# BMW_final_CH_Label.net
KiCad netlist of a schematic drawn in EAGLE
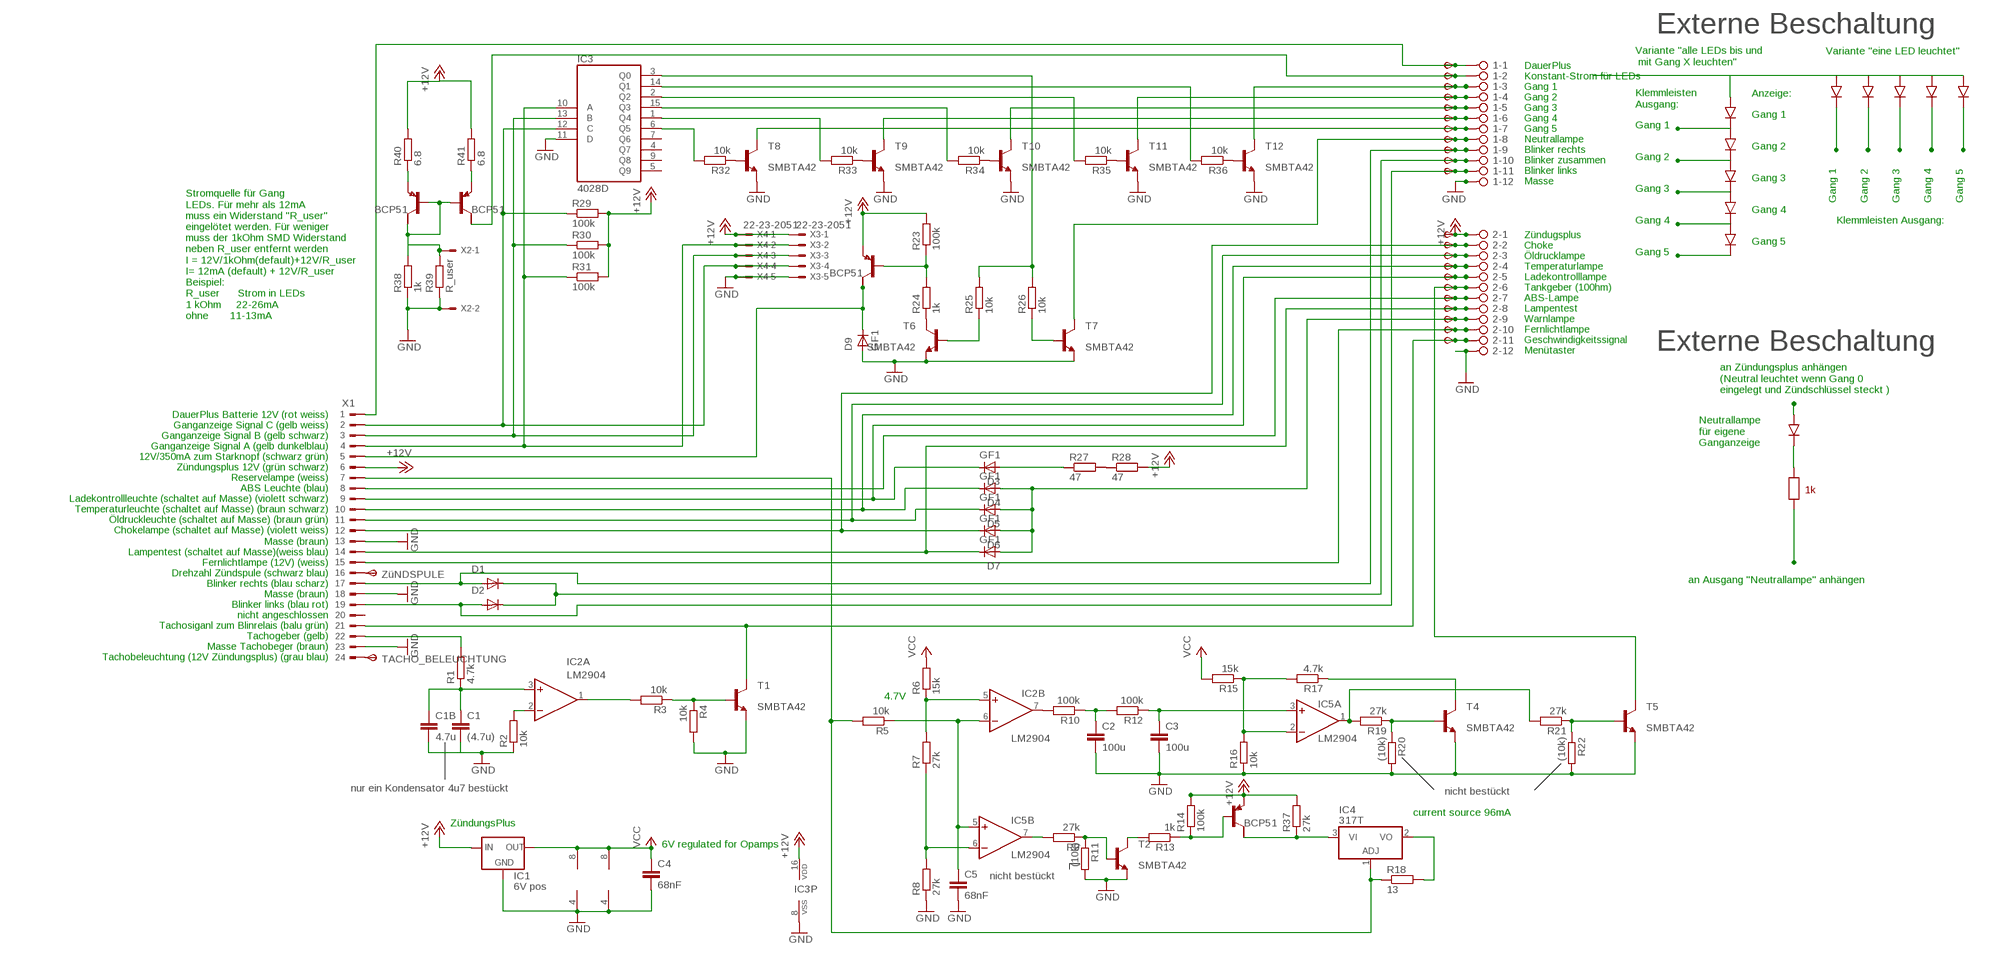
[diagram p0: schematic, sheet 1]

(export (version "E")
  (design (tool "Eeschema 10.0.6"))
  (components
    (comp (ref "1")
      (value "2081-1132")
      (footprint "eagle-import:12-PIN")
      (libsource (lib "eagle-import") (part "2081-1132"))
    )
    (comp (ref "2")
      (value "2081-1132")
      (footprint "eagle-import:12-PIN")
      (libsource (lib "eagle-import") (part "2081-1132"))
    )
    (comp (ref "C1")
      (value "(4.7u)")
      (footprint "eagle-import:C1206")
      (libsource (lib "eagle-import") (part "C-EUC1206"))
    )
    (comp (ref "C1B")
      (value "4.7u")
      (footprint "eagle-import:C0805K")
      (libsource (lib "eagle-import") (part "C-EUC0805K"))
    )
    (comp (ref "C2")
      (value "100u")
      (footprint "eagle-import:C1206K")
      (libsource (lib "eagle-import") (part "C-EUC1206K"))
    )
    (comp (ref "C3")
      (value "100u")
      (footprint "eagle-import:C1206K")
      (libsource (lib "eagle-import") (part "C-EUC1206K"))
    )
    (comp (ref "C4")
      (value "68nF")
      (footprint "eagle-import:C1206K")
      (libsource (lib "eagle-import") (part "C-EUC1206K"))
    )
    (comp (ref "C5")
      (value "68nF")
      (footprint "eagle-import:C1206K")
      (libsource (lib "eagle-import") (part "C-EUC1206K"))
    )
    (comp (ref "D1")
      (value "GF1")
      (footprint "eagle-import:SMA-DO214AC")
      (libsource (lib "eagle-import") (part "GF1"))
    )
    (comp (ref "D2")
      (value "GF1")
      (footprint "eagle-import:SMA-DO214AC")
      (libsource (lib "eagle-import") (part "GF1"))
    )
    (comp (ref "D3")
      (value "GF1")
      (footprint "eagle-import:SMA-DO214AC")
      (libsource (lib "eagle-import") (part "GF1"))
    )
    (comp (ref "D4")
      (value "GF1")
      (footprint "eagle-import:SMA-DO214AC")
      (libsource (lib "eagle-import") (part "GF1"))
    )
    (comp (ref "D5")
      (value "GF1")
      (footprint "eagle-import:SMA-DO214AC")
      (libsource (lib "eagle-import") (part "GF1"))
    )
    (comp (ref "D6")
      (value "GF1")
      (footprint "eagle-import:SMA-DO214AC")
      (libsource (lib "eagle-import") (part "GF1"))
    )
    (comp (ref "D7")
      (value "GF1")
      (footprint "eagle-import:SMA-DO214AC")
      (libsource (lib "eagle-import") (part "GF1"))
    )
    (comp (ref "D9")
      (value "GF1")
      (footprint "eagle-import:SMA-DO214AC")
      (libsource (lib "eagle-import") (part "GF1"))
    )
    (comp (ref "IC1")
      (value "6V pos")
      (footprint "eagle-import:78LXX")
      (libsource (lib "eagle-import") (part "78LXX"))
    )
    (comp (ref "IC2")
      (value "LM2904")
      (footprint "eagle-import:SO08")
      (fields (field (name "IC") "LM2904"))
      (libsource (lib "eagle-import") (part "LM358D"))
    )
    (comp (ref "IC3")
      (value "4028D")
      (footprint "eagle-import:SO16")
      (libsource (lib "eagle-import") (part "4028D"))
    )
    (comp (ref "IC4")
      (value "317T")
      (footprint "eagle-import:TO220H")
      (libsource (lib "eagle-import") (part "317T"))
    )
    (comp (ref "IC5")
      (value "LM2904")
      (footprint "eagle-import:SO08")
      (libsource (lib "eagle-import") (part "linear_BMW_LM358D"))
    )
    (comp (ref "R1")
      (value "4.7k")
      (footprint "eagle-import:R0805")
      (libsource (lib "eagle-import") (part "R-EU_R0805"))
    )
    (comp (ref "R2")
      (value "10k")
      (footprint "eagle-import:R0805")
      (libsource (lib "eagle-import") (part "R-EU_R0805"))
    )
    (comp (ref "R3")
      (value "10k")
      (footprint "eagle-import:R0805")
      (libsource (lib "eagle-import") (part "R-EU_R0805"))
    )
    (comp (ref "R4")
      (value "10k")
      (footprint "eagle-import:R0805")
      (libsource (lib "eagle-import") (part "R-EU_R0805"))
    )
    (comp (ref "R5")
      (value "10k")
      (footprint "eagle-import:R0805")
      (libsource (lib "eagle-import") (part "R-EU_R0805"))
    )
    (comp (ref "R6")
      (value "15k")
      (footprint "eagle-import:R0805")
      (libsource (lib "eagle-import") (part "R-EU_R0805"))
    )
    (comp (ref "R7")
      (value "27k")
      (footprint "eagle-import:R0805")
      (libsource (lib "eagle-import") (part "R-EU_R0805"))
    )
    (comp (ref "R8")
      (value "27k")
      (footprint "eagle-import:R0805")
      (libsource (lib "eagle-import") (part "R-EU_R0805"))
    )
    (comp (ref "R9")
      (value "27k")
      (footprint "eagle-import:R0805")
      (libsource (lib "eagle-import") (part "R-EU_R0805"))
    )
    (comp (ref "R10")
      (value "100k")
      (footprint "eagle-import:R0805")
      (libsource (lib "eagle-import") (part "R-EU_R0805"))
    )
    (comp (ref "R11")
      (value "(10k)")
      (footprint "eagle-import:R0805")
      (libsource (lib "eagle-import") (part "R-EU_R0805"))
    )
    (comp (ref "R12")
      (value "100k")
      (footprint "eagle-import:R0805")
      (libsource (lib "eagle-import") (part "R-EU_R0805"))
    )
    (comp (ref "R13")
      (value "1k")
      (footprint "eagle-import:R0805")
      (libsource (lib "eagle-import") (part "R-EU_R0805"))
    )
    (comp (ref "R14")
      (value "100k")
      (footprint "eagle-import:R0805")
      (libsource (lib "eagle-import") (part "R-EU_R0805"))
    )
    (comp (ref "R15")
      (value "15k")
      (footprint "eagle-import:R0805")
      (libsource (lib "eagle-import") (part "R-EU_R0805"))
    )
    (comp (ref "R16")
      (value "10k")
      (footprint "eagle-import:R0805")
      (libsource (lib "eagle-import") (part "R-EU_R0805"))
    )
    (comp (ref "R17")
      (value "4.7k")
      (footprint "eagle-import:R0805")
      (libsource (lib "eagle-import") (part "R-EU_R0805"))
    )
    (comp (ref "R18")
      (value "13")
      (footprint "eagle-import:0207_10")
      (libsource (lib "eagle-import") (part "R-EU_0207/10"))
    )
    (comp (ref "R19")
      (value "27k")
      (footprint "eagle-import:R0805")
      (libsource (lib "eagle-import") (part "R-EU_R0805"))
    )
    (comp (ref "R20")
      (value "(10k)")
      (footprint "eagle-import:R0805")
      (libsource (lib "eagle-import") (part "R-EU_R0805"))
    )
    (comp (ref "R21")
      (value "27k")
      (footprint "eagle-import:R0805")
      (libsource (lib "eagle-import") (part "R-EU_R0805"))
    )
    (comp (ref "R22")
      (value "(10k)")
      (footprint "eagle-import:R0805")
      (libsource (lib "eagle-import") (part "R-EU_R0805"))
    )
    (comp (ref "R23")
      (value "100k")
      (footprint "eagle-import:R0805")
      (libsource (lib "eagle-import") (part "R-EU_R0805"))
    )
    (comp (ref "R24")
      (value "1k")
      (footprint "eagle-import:R0805")
      (libsource (lib "eagle-import") (part "R-EU_R0805"))
    )
    (comp (ref "R25")
      (value "10k")
      (footprint "eagle-import:R0805")
      (libsource (lib "eagle-import") (part "R-EU_R0805"))
    )
    (comp (ref "R26")
      (value "10k")
      (footprint "eagle-import:R0805")
      (libsource (lib "eagle-import") (part "R-EU_R0805"))
    )
    (comp (ref "R27")
      (value "47")
      (footprint "eagle-import:V235_17")
      (libsource (lib "eagle-import") (part "R-EU_V235/17"))
    )
    (comp (ref "R28")
      (value "47")
      (footprint "eagle-import:V235_17")
      (libsource (lib "eagle-import") (part "R-EU_V235/17"))
    )
    (comp (ref "R29")
      (value "100k")
      (footprint "eagle-import:R0805")
      (libsource (lib "eagle-import") (part "R-EU_R0805"))
    )
    (comp (ref "R30")
      (value "100k")
      (footprint "eagle-import:R0805")
      (libsource (lib "eagle-import") (part "R-EU_R0805"))
    )
    (comp (ref "R31")
      (value "100k")
      (footprint "eagle-import:R0805")
      (libsource (lib "eagle-import") (part "R-EU_R0805"))
    )
    (comp (ref "R32")
      (value "10k")
      (footprint "eagle-import:R0805")
      (libsource (lib "eagle-import") (part "R-EU_R0805"))
    )
    (comp (ref "R33")
      (value "10k")
      (footprint "eagle-import:R0805")
      (libsource (lib "eagle-import") (part "R-EU_R0805"))
    )
    (comp (ref "R34")
      (value "10k")
      (footprint "eagle-import:R0805")
      (libsource (lib "eagle-import") (part "R-EU_R0805"))
    )
    (comp (ref "R35")
      (value "10k")
      (footprint "eagle-import:R0805")
      (libsource (lib "eagle-import") (part "R-EU_R0805"))
    )
    (comp (ref "R36")
      (value "10k")
      (footprint "eagle-import:R0805")
      (libsource (lib "eagle-import") (part "R-EU_R0805"))
    )
    (comp (ref "R37")
      (value "27k")
      (footprint "eagle-import:R0805")
      (libsource (lib "eagle-import") (part "R-EU_R0805"))
    )
    (comp (ref "R38")
      (value "1k")
      (footprint "eagle-import:R0805")
      (libsource (lib "eagle-import") (part "R-EU_R0805"))
    )
    (comp (ref "R39")
      (value "R_user")
      (footprint "eagle-import:R0805")
      (libsource (lib "eagle-import") (part "R-EU_R0805"))
    )
    (comp (ref "R40")
      (value "6.8")
      (footprint "eagle-import:R0805")
      (libsource (lib "eagle-import") (part "R-EU_R0805"))
    )
    (comp (ref "R41")
      (value "6.8")
      (footprint "eagle-import:R0805")
      (libsource (lib "eagle-import") (part "R-EU_R0805"))
    )
    (comp (ref "T")
      (value "BCP53T1")
      (footprint "eagle-import:SOT223")
      (fields (field (name "T") "BCP51"))
      (libsource (lib "eagle-import") (part "BCP53T1"))
    )
    (comp (ref "T1")
      (value "MMBTA42LT1-NPN-SOT23-BEC")
      (footprint "eagle-import:SOT23-BEC")
      (fields (field (name "T") "SMBTA42"))
      (libsource (lib "eagle-import") (part "-NPN-SOT23-BECMMBTA42LT1"))
    )
    (comp (ref "T2")
      (value "MMBTA42LT1-NPN-SOT23-BEC")
      (footprint "eagle-import:SOT23-BEC")
      (fields (field (name "T") "SMBTA42"))
      (libsource (lib "eagle-import") (part "-NPN-SOT23-BECMMBTA42LT1"))
    )
    (comp (ref "T3")
      (value "BCP53T1")
      (footprint "eagle-import:SOT223")
      (fields (field (name "T") "BCP51"))
      (libsource (lib "eagle-import") (part "BCP53T1"))
    )
    (comp (ref "T4")
      (value "MMBTA42LT1-NPN-SOT23-BEC")
      (footprint "eagle-import:SOT23-BEC")
      (fields (field (name "T") "SMBTA42"))
      (libsource (lib "eagle-import") (part "-NPN-SOT23-BECMMBTA42LT1"))
    )
    (comp (ref "T5")
      (value "MMBTA42LT1-NPN-SOT23-BEC")
      (footprint "eagle-import:SOT23-BEC")
      (fields (field (name "T") "SMBTA42"))
      (libsource (lib "eagle-import") (part "-NPN-SOT23-BECMMBTA42LT1"))
    )
    (comp (ref "T6")
      (value "MMBTA42LT1-NPN-SOT23-BEC")
      (footprint "eagle-import:SOT23-BEC")
      (fields (field (name "T") "SMBTA42"))
      (libsource (lib "eagle-import") (part "-NPN-SOT23-BECMMBTA42LT1"))
    )
    (comp (ref "T7")
      (value "MMBTA42LT1-NPN-SOT23-BEC")
      (footprint "eagle-import:SOT23-BEC")
      (fields (field (name "T") "SMBTA42"))
      (libsource (lib "eagle-import") (part "-NPN-SOT23-BECMMBTA42LT1"))
    )
    (comp (ref "T8")
      (value "MMBTA42LT1-NPN-SOT23-BEC")
      (footprint "eagle-import:SOT23-BEC")
      (fields (field (name "T") "SMBTA42"))
      (libsource (lib "eagle-import") (part "-NPN-SOT23-BECMMBTA42LT1"))
    )
    (comp (ref "T9")
      (value "MMBTA42LT1-NPN-SOT23-BEC")
      (footprint "eagle-import:SOT23-BEC")
      (fields (field (name "T") "SMBTA42"))
      (libsource (lib "eagle-import") (part "-NPN-SOT23-BECMMBTA42LT1"))
    )
    (comp (ref "T10")
      (value "MMBTA42LT1-NPN-SOT23-BEC")
      (footprint "eagle-import:SOT23-BEC")
      (fields (field (name "T") "SMBTA42"))
      (libsource (lib "eagle-import") (part "-NPN-SOT23-BECMMBTA42LT1"))
    )
    (comp (ref "T11")
      (value "MMBTA42LT1-NPN-SOT23-BEC")
      (footprint "eagle-import:SOT23-BEC")
      (fields (field (name "T") "SMBTA42"))
      (libsource (lib "eagle-import") (part "-NPN-SOT23-BECMMBTA42LT1"))
    )
    (comp (ref "T12")
      (value "MMBTA42LT1-NPN-SOT23-BEC")
      (footprint "eagle-import:SOT23-BEC")
      (fields (field (name "T") "SMBTA42"))
      (libsource (lib "eagle-import") (part "-NPN-SOT23-BECMMBTA42LT1"))
    )
    (comp (ref "T13")
      (value "BCP53T1")
      (footprint "eagle-import:SOT223")
      (fields (field (name "T") "BCP51"))
      (libsource (lib "eagle-import") (part "BCP53T1"))
    )
    (comp (ref "T14")
      (value "BCP53T1")
      (footprint "eagle-import:SOT223")
      (fields (field (name "T") "BCP51"))
      (libsource (lib "eagle-import") (part "BCP53T1"))
    )
    (comp (ref "TACHO_BELEUCHTUNG")
      (value "TPSP1_1MM")
      (footprint "eagle-import:P1_1.0MM")
      (libsource (lib "eagle-import") (part "TPSP1_1MM"))
    )
    (comp (ref "TP1")
      (value "TPSB1,27")
      (footprint "eagle-import:B1,27")
      (libsource (lib "eagle-import") (part "TPSB1,27"))
    )
    (comp (ref "TP2")
      (value "TPSB1,27")
      (footprint "eagle-import:B1,27")
      (libsource (lib "eagle-import") (part "TPSB1,27"))
    )
    (comp (ref "TP3")
      (value "TPSB1,27")
      (footprint "eagle-import:B1,27")
      (libsource (lib "eagle-import") (part "TPSB1,27"))
    )
    (comp (ref "TP4")
      (value "TPSB1,27")
      (footprint "eagle-import:B1,27")
      (libsource (lib "eagle-import") (part "TPSB1,27"))
    )
    (comp (ref "TP5")
      (value "TPSB1,27")
      (footprint "eagle-import:B1,27")
      (libsource (lib "eagle-import") (part "TPSB1,27"))
    )
    (comp (ref "TP6")
      (value "TPSB1,27")
      (footprint "eagle-import:B1,27")
      (libsource (lib "eagle-import") (part "TPSB1,27"))
    )
    (comp (ref "TP7")
      (value "TPSB1,27")
      (footprint "eagle-import:B1,27")
      (libsource (lib "eagle-import") (part "TPSB1,27"))
    )
    (comp (ref "TP8")
      (value "TPSB1,27")
      (footprint "eagle-import:B1,27")
      (libsource (lib "eagle-import") (part "TPSB1,27"))
    )
    (comp (ref "TP9")
      (value "TPSB1,27")
      (footprint "eagle-import:B1,27")
      (libsource (lib "eagle-import") (part "TPSB1,27"))
    )
    (comp (ref "TP10")
      (value "TPSB1,27")
      (footprint "eagle-import:B1,27")
      (libsource (lib "eagle-import") (part "TPSB1,27"))
    )
    (comp (ref "TP11")
      (value "TPSB1,27")
      (footprint "eagle-import:B1,27")
      (libsource (lib "eagle-import") (part "TPSB1,27"))
    )
    (comp (ref "TP12")
      (value "TPSB1,27")
      (footprint "eagle-import:B1,27")
      (libsource (lib "eagle-import") (part "TPSB1,27"))
    )
    (comp (ref "TP16")
      (value "TPSB1,27")
      (footprint "eagle-import:B1,27")
      (libsource (lib "eagle-import") (part "TPSB1,27"))
    )
    (comp (ref "TP17")
      (value "TPSB1,27")
      (footprint "eagle-import:B1,27")
      (libsource (lib "eagle-import") (part "TPSB1,27"))
    )
    (comp (ref "TP18")
      (value "TPSB1,27")
      (footprint "eagle-import:B1,27")
      (libsource (lib "eagle-import") (part "TPSB1,27"))
    )
    (comp (ref "TP19")
      (value "TPSB1,27")
      (footprint "eagle-import:B1,27")
      (libsource (lib "eagle-import") (part "TPSB1,27"))
    )
    (comp (ref "TP21")
      (value "TPSB1,27")
      (footprint "eagle-import:B1,27")
      (libsource (lib "eagle-import") (part "TPSB1,27"))
    )
    (comp (ref "TP22")
      (value "TPSB1,27")
      (footprint "eagle-import:B1,27")
      (libsource (lib "eagle-import") (part "TPSB1,27"))
    )
    (comp (ref "TP23")
      (value "TPSB1,27")
      (footprint "eagle-import:B1,27")
      (libsource (lib "eagle-import") (part "TPSB1,27"))
    )
    (comp (ref "TP24")
      (value "TPSB1,27")
      (footprint "eagle-import:B1,27")
      (libsource (lib "eagle-import") (part "TPSB1,27"))
    )
    (comp (ref "TP25")
      (value "TPSB1,27")
      (footprint "eagle-import:B1,27")
      (libsource (lib "eagle-import") (part "TPSB1,27"))
    )
    (comp (ref "TP26")
      (value "TPSB1,27")
      (footprint "eagle-import:B1,27")
      (libsource (lib "eagle-import") (part "TPSB1,27"))
    )
    (comp (ref "X1")
      (value "CON_BMW")
      (footprint "eagle-import:24-PIN")
      (libsource (lib "eagle-import") (part "CON_BMW"))
    )
    (comp (ref "X2")
      (value "22-23-2021")
      (footprint "eagle-import:22-23-2021")
      (fields (field (name "MF") "MOLEX"))
      (libsource (lib "eagle-import") (part "22-23-2021"))
    )
    (comp (ref "X3")
      (value "22-23-2051")
      (footprint "eagle-import:22-23-2051")
      (fields (field (name "MF") "MOLEX"))
      (libsource (lib "eagle-import") (part "22-23-2051"))
    )
    (comp (ref "X4")
      (value "22-23-2051")
      (footprint "eagle-import:22-23-2051")
      (fields (field (name "MF") "MOLEX"))
      (libsource (lib "eagle-import") (part "22-23-2051"))
    )
    (comp (ref "ZüNDSPULE")
      (value "TPSP1_1MM")
      (footprint "eagle-import:P1_1.0MM")
      (libsource (lib "eagle-import") (part "TPSP1_1MM"))
    )
  )
  (nets
    (net (code "1") (name "+12V") (class "Default")
      (node (ref "2") (pin "1") (pinfunction "KL_1") (pintype "passive"))
      (node (ref "IC1") (pin "IN") (pinfunction "IN_IN") (pintype "input"))
      (node (ref "IC3") (pin "16") (pinfunction "VDD_16") (pintype "power_in"))
      (node (ref "R14") (pin "2") (pinfunction "2_2") (pintype "passive"))
      (node (ref "R23") (pin "2") (pinfunction "2_2") (pintype "passive"))
      (node (ref "R28") (pin "2") (pinfunction "2_2") (pintype "passive"))
      (node (ref "R29") (pin "2") (pinfunction "2_2") (pintype "passive"))
      (node (ref "R30") (pin "2") (pinfunction "2_2") (pintype "passive"))
      (node (ref "R31") (pin "2") (pinfunction "2_2") (pintype "passive"))
      (node (ref "R37") (pin "2") (pinfunction "2_2") (pintype "passive"))
      (node (ref "R40") (pin "2") (pinfunction "2_2") (pintype "passive"))
      (node (ref "R41") (pin "2") (pinfunction "2_2") (pintype "passive"))
      (node (ref "T") (pin "3") (pinfunction "E_3") (pintype "passive"))
      (node (ref "T3") (pin "3") (pinfunction "E_3") (pintype "passive"))
      (node (ref "TP12") (pin "TP") (pinfunction "PP_TP") (pintype "input"))
      (node (ref "X1") (pin "6") (pinfunction "6_6") (pintype "passive"))
      (node (ref "X3") (pin "1") (pinfunction "S_1") (pintype "passive"))
      (node (ref "X4") (pin "1") (pinfunction "S_1") (pintype "passive"))
    )
    (net (code "2") (name "GND") (class "Default")
      (node (ref "1") (pin "12") (pinfunction "KL_12") (pintype "passive"))
      (node (ref "2") (pin "12") (pinfunction "KL_12") (pintype "passive"))
      (node (ref "C1") (pin "2") (pinfunction "2_2") (pintype "passive"))
      (node (ref "C1B") (pin "2") (pinfunction "2_2") (pintype "passive"))
      (node (ref "C2") (pin "2") (pinfunction "2_2") (pintype "passive"))
      (node (ref "C3") (pin "2") (pinfunction "2_2") (pintype "passive"))
      (node (ref "C4") (pin "2") (pinfunction "2_2") (pintype "passive"))
      (node (ref "C5") (pin "2") (pinfunction "2_2") (pintype "passive"))
      (node (ref "D9") (pin "A") (pinfunction "A_A") (pintype "passive"))
      (node (ref "IC1") (pin "GND") (pinfunction "GND_GND") (pintype "input"))
      (node (ref "IC2") (pin "4") (pinfunction "V-_4") (pintype "power_in"))
      (node (ref "IC3") (pin "11") (pinfunction "D_11") (pintype "input"))
      (node (ref "IC3") (pin "8") (pinfunction "VSS_8") (pintype "power_in"))
      (node (ref "IC5") (pin "4") (pinfunction "V-_4") (pintype "power_in"))
      (node (ref "R11") (pin "2") (pinfunction "2_2") (pintype "passive"))
      (node (ref "R16") (pin "1") (pinfunction "1_1") (pintype "passive"))
      (node (ref "R2") (pin "1") (pinfunction "1_1") (pintype "passive"))
      (node (ref "R20") (pin "2") (pinfunction "2_2") (pintype "passive"))
      (node (ref "R22") (pin "2") (pinfunction "2_2") (pintype "passive"))
      (node (ref "R38") (pin "1") (pinfunction "1_1") (pintype "passive"))
      (node (ref "R39") (pin "1") (pinfunction "1_1") (pintype "passive"))
      (node (ref "R4") (pin "2") (pinfunction "2_2") (pintype "passive"))
      (node (ref "R8") (pin "1") (pinfunction "1_1") (pintype "passive"))
      (node (ref "T1") (pin "E") (pinfunction "E_E") (pintype "passive"))
      (node (ref "T10") (pin "E") (pinfunction "E_E") (pintype "passive"))
      (node (ref "T11") (pin "E") (pinfunction "E_E") (pintype "passive"))
      (node (ref "T12") (pin "E") (pinfunction "E_E") (pintype "passive"))
      (node (ref "T2") (pin "E") (pinfunction "E_E") (pintype "passive"))
      (node (ref "T4") (pin "E") (pinfunction "E_E") (pintype "passive"))
      (node (ref "T5") (pin "E") (pinfunction "E_E") (pintype "passive"))
      (node (ref "T6") (pin "E") (pinfunction "E_E") (pintype "passive"))
      (node (ref "T7") (pin "E") (pinfunction "E_E") (pintype "passive"))
      (node (ref "T8") (pin "E") (pinfunction "E_E") (pintype "passive"))
      (node (ref "T9") (pin "E") (pinfunction "E_E") (pintype "passive"))
      (node (ref "X1") (pin "13") (pinfunction "13_13") (pintype "passive"))
      (node (ref "X1") (pin "18") (pinfunction "18_18") (pintype "passive"))
      (node (ref "X1") (pin "23") (pinfunction "23_23") (pintype "passive"))
      (node (ref "X2") (pin "2") (pinfunction "S_2") (pintype "passive"))
      (node (ref "X3") (pin "5") (pinfunction "S_5") (pintype "passive"))
      (node (ref "X4") (pin "5") (pinfunction "S_5") (pintype "passive"))
    )
    (net (code "3") (name "Net-(1A-KL)") (class "Default")
      (node (ref "1") (pin "1") (pinfunction "KL_1") (pintype "passive"))
      (node (ref "TP1") (pin "TP") (pinfunction "PP_TP") (pintype "input"))
      (node (ref "X1") (pin "1") (pinfunction "1_1") (pintype "passive"))
    )
    (net (code "4") (name "Net-(1B-KL)") (class "Default")
      (node (ref "1") (pin "10") (pinfunction "KL_10") (pintype "passive"))
      (node (ref "D1") (pin "K") (pinfunction "C_K") (pintype "passive"))
      (node (ref "D2") (pin "K") (pinfunction "C_K") (pintype "passive"))
      (node (ref "TP10") (pin "TP") (pinfunction "PP_TP") (pintype "input"))
    )
    (net (code "5") (name "Net-(1C-KL)") (class "Default")
      (node (ref "1") (pin "11") (pinfunction "KL_11") (pintype "passive"))
      (node (ref "D2") (pin "A") (pinfunction "A_A") (pintype "passive"))
      (node (ref "TP11") (pin "TP") (pinfunction "PP_TP") (pintype "input"))
      (node (ref "X1") (pin "19") (pinfunction "19_19") (pintype "passive"))
    )
    (net (code "6") (name "Net-(1E-KL)") (class "Default")
      (node (ref "1") (pin "2") (pinfunction "KL_2") (pintype "passive"))
      (node (ref "T14") (pin "2") (pinfunction "C_2") (pintype "passive"))
      (node (ref "TP2") (pin "TP") (pinfunction "PP_TP") (pintype "input"))
    )
    (net (code "7") (name "Net-(1F-KL)") (class "Default")
      (node (ref "1") (pin "3") (pinfunction "KL_3") (pintype "passive"))
      (node (ref "T12") (pin "C") (pinfunction "C_C") (pintype "passive"))
      (node (ref "TP3") (pin "TP") (pinfunction "PP_TP") (pintype "input"))
    )
    (net (code "8") (name "Net-(1G-KL)") (class "Default")
      (node (ref "1") (pin "4") (pinfunction "KL_4") (pintype "passive"))
      (node (ref "T11") (pin "C") (pinfunction "C_C") (pintype "passive"))
      (node (ref "TP4") (pin "TP") (pinfunction "PP_TP") (pintype "input"))
    )
    (net (code "9") (name "Net-(1H-KL)") (class "Default")
      (node (ref "1") (pin "5") (pinfunction "KL_5") (pintype "passive"))
      (node (ref "T10") (pin "C") (pinfunction "C_C") (pintype "passive"))
      (node (ref "TP5") (pin "TP") (pinfunction "PP_TP") (pintype "input"))
    )
    (net (code "10") (name "Net-(1I-KL)") (class "Default")
      (node (ref "1") (pin "6") (pinfunction "KL_6") (pintype "passive"))
      (node (ref "T9") (pin "C") (pinfunction "C_C") (pintype "passive"))
      (node (ref "TP6") (pin "TP") (pinfunction "PP_TP") (pintype "input"))
    )
    (net (code "11") (name "Net-(1J-KL)") (class "Default")
      (node (ref "1") (pin "7") (pinfunction "KL_7") (pintype "passive"))
      (node (ref "T8") (pin "C") (pinfunction "C_C") (pintype "passive"))
      (node (ref "TP7") (pin "TP") (pinfunction "PP_TP") (pintype "input"))
    )
    (net (code "12") (name "Net-(1K-KL)") (class "Default")
      (node (ref "1") (pin "8") (pinfunction "KL_8") (pintype "passive"))
      (node (ref "T7") (pin "C") (pinfunction "C_C") (pintype "passive"))
      (node (ref "TP8") (pin "TP") (pinfunction "PP_TP") (pintype "input"))
    )
    (net (code "13") (name "Net-(1L-KL)") (class "Default")
      (node (ref "1") (pin "9") (pinfunction "KL_9") (pintype "passive"))
      (node (ref "D1") (pin "A") (pinfunction "A_A") (pintype "passive"))
      (node (ref "TP9") (pin "TP") (pinfunction "PP_TP") (pintype "input"))
      (node (ref "X1") (pin "17") (pinfunction "17_17") (pintype "passive"))
    )
    (net (code "14") (name "Net-(2B-KL)") (class "Default")
      (node (ref "2") (pin "10") (pinfunction "KL_10") (pintype "passive"))
      (node (ref "TP25") (pin "TP") (pinfunction "PP_TP") (pintype "input"))
      (node (ref "X1") (pin "15") (pinfunction "15_15") (pintype "passive"))
    )
    (net (code "15") (name "Net-(2C-KL)") (class "Default")
      (node (ref "2") (pin "11") (pinfunction "KL_11") (pintype "passive"))
      (node (ref "T1") (pin "C") (pinfunction "C_C") (pintype "passive"))
      (node (ref "TP26") (pin "TP") (pinfunction "PP_TP") (pintype "input"))
      (node (ref "X1") (pin "21") (pinfunction "21_21") (pintype "passive"))
    )
    (net (code "16") (name "Net-(2E-KL)") (class "Default")
      (node (ref "2") (pin "2") (pinfunction "KL_2") (pintype "passive"))
      (node (ref "D6") (pin "K") (pinfunction "C_K") (pintype "passive"))
      (node (ref "TP16") (pin "TP") (pinfunction "PP_TP") (pintype "input"))
      (node (ref "X1") (pin "12") (pinfunction "12_12") (pintype "passive"))
    )
    (net (code "17") (name "Net-(2F-KL)") (class "Default")
      (node (ref "2") (pin "3") (pinfunction "KL_3") (pintype "passive"))
      (node (ref "D5") (pin "K") (pinfunction "C_K") (pintype "passive"))
      (node (ref "TP17") (pin "TP") (pinfunction "PP_TP") (pintype "input"))
      (node (ref "X1") (pin "11") (pinfunction "11_11") (pintype "passive"))
    )
    (net (code "18") (name "Net-(2G-KL)") (class "Default")
      (node (ref "2") (pin "4") (pinfunction "KL_4") (pintype "passive"))
      (node (ref "D4") (pin "K") (pinfunction "C_K") (pintype "passive"))
      (node (ref "TP18") (pin "TP") (pinfunction "PP_TP") (pintype "input"))
      (node (ref "X1") (pin "10") (pinfunction "10_10") (pintype "passive"))
    )
    (net (code "19") (name "Net-(2H-KL)") (class "Default")
      (node (ref "2") (pin "5") (pinfunction "KL_5") (pintype "passive"))
      (node (ref "D3") (pin "K") (pinfunction "C_K") (pintype "passive"))
      (node (ref "TP19") (pin "TP") (pinfunction "PP_TP") (pintype "input"))
      (node (ref "X1") (pin "9") (pinfunction "9_9") (pintype "passive"))
    )
    (net (code "20") (name "Net-(2I-KL)") (class "Default")
      (node (ref "2") (pin "6") (pinfunction "KL_6") (pintype "passive"))
      (node (ref "T5") (pin "C") (pinfunction "C_C") (pintype "passive"))
      (node (ref "TP21") (pin "TP") (pinfunction "PP_TP") (pintype "input"))
    )
    (net (code "21") (name "Net-(2J-KL)") (class "Default")
      (node (ref "2") (pin "7") (pinfunction "KL_7") (pintype "passive"))
      (node (ref "TP22") (pin "TP") (pinfunction "PP_TP") (pintype "input"))
      (node (ref "X1") (pin "8") (pinfunction "8_8") (pintype "passive"))
    )
    (net (code "22") (name "Net-(2K-KL)") (class "Default")
      (node (ref "2") (pin "8") (pinfunction "KL_8") (pintype "passive"))
      (node (ref "D7") (pin "K") (pinfunction "C_K") (pintype "passive"))
      (node (ref "TP23") (pin "TP") (pinfunction "PP_TP") (pintype "input"))
      (node (ref "X1") (pin "14") (pinfunction "14_14") (pintype "passive"))
    )
    (net (code "23") (name "Net-(2L-KL)") (class "Default")
      (node (ref "2") (pin "9") (pinfunction "KL_9") (pintype "passive"))
      (node (ref "D4") (pin "A") (pinfunction "A_A") (pintype "passive"))
      (node (ref "D5") (pin "A") (pinfunction "A_A") (pintype "passive"))
      (node (ref "D6") (pin "A") (pinfunction "A_A") (pintype "passive"))
      (node (ref "D7") (pin "A") (pinfunction "A_A") (pintype "passive"))
      (node (ref "TP24") (pin "TP") (pinfunction "PP_TP") (pintype "input"))
    )
    (net (code "24") (name "Net-(C2-Pad1)") (class "Default")
      (node (ref "C2") (pin "1") (pinfunction "1_1") (pintype "passive"))
      (node (ref "R10") (pin "1") (pinfunction "1_1") (pintype "passive"))
      (node (ref "R12") (pin "2") (pinfunction "2_2") (pintype "passive"))
    )
    (net (code "25") (name "Net-(D3-PadA)") (class "Default")
      (node (ref "D3") (pin "A") (pinfunction "A_A") (pintype "passive"))
      (node (ref "R27") (pin "1") (pinfunction "1_1") (pintype "passive"))
    )
    (net (code "26") (name "Net-(D9-C)") (class "Default")
      (node (ref "D9") (pin "K") (pinfunction "C_K") (pintype "passive"))
      (node (ref "T") (pin "2") (pinfunction "C_2") (pintype "passive"))
      (node (ref "X1") (pin "5") (pinfunction "5_5") (pintype "passive"))
    )
    (net (code "27") (name "Net-(IC2A-+IN)") (class "Default")
      (node (ref "C1") (pin "1") (pinfunction "1_1") (pintype "passive"))
      (node (ref "C1B") (pin "1") (pinfunction "1_1") (pintype "passive"))
      (node (ref "IC2") (pin "3") (pinfunction "+IN_3") (pintype "input"))
      (node (ref "R1") (pin "1") (pinfunction "1_1") (pintype "passive"))
    )
    (net (code "28") (name "Net-(IC2A--IN)") (class "Default")
      (node (ref "IC2") (pin "2") (pinfunction "-IN_2") (pintype "input"))
      (node (ref "R2") (pin "2") (pinfunction "2_2") (pintype "passive"))
    )
    (net (code "29") (name "Net-(IC2A-OUT)") (class "Default")
      (node (ref "IC2") (pin "1") (pinfunction "OUT_1") (pintype "output"))
      (node (ref "R3") (pin "2") (pinfunction "2_2") (pintype "passive"))
    )
    (net (code "30") (name "Net-(IC2B-+IN)") (class "Default")
      (node (ref "IC2") (pin "5") (pinfunction "+IN_5") (pintype "input"))
      (node (ref "R6") (pin "1") (pinfunction "1_1") (pintype "passive"))
      (node (ref "R7") (pin "2") (pinfunction "2_2") (pintype "passive"))
    )
    (net (code "31") (name "Net-(IC2B--IN)") (class "Default")
      (node (ref "C5") (pin "1") (pinfunction "1_1") (pintype "passive"))
      (node (ref "IC2") (pin "6") (pinfunction "-IN_6") (pintype "input"))
      (node (ref "IC5") (pin "5") (pinfunction "+IN_5") (pintype "input"))
      (node (ref "R5") (pin "1") (pinfunction "1_1") (pintype "passive"))
    )
    (net (code "32") (name "Net-(IC2B-OUT)") (class "Default")
      (node (ref "IC2") (pin "7") (pinfunction "OUT_7") (pintype "output"))
      (node (ref "R10") (pin "2") (pinfunction "2_2") (pintype "passive"))
    )
    (net (code "33") (name "Net-(IC3A-A)") (class "Default")
      (node (ref "IC3") (pin "10") (pinfunction "A_10") (pintype "input"))
      (node (ref "R31") (pin "1") (pinfunction "1_1") (pintype "passive"))
      (node (ref "X1") (pin "4") (pinfunction "4_4") (pintype "passive"))
      (node (ref "X3") (pin "2") (pinfunction "S_2") (pintype "passive"))
      (node (ref "X4") (pin "2") (pinfunction "S_2") (pintype "passive"))
    )
    (net (code "34") (name "Net-(IC3A-B)") (class "Default")
      (node (ref "IC3") (pin "13") (pinfunction "B_13") (pintype "input"))
      (node (ref "R30") (pin "1") (pinfunction "1_1") (pintype "passive"))
      (node (ref "X1") (pin "3") (pinfunction "3_3") (pintype "passive"))
      (node (ref "X3") (pin "3") (pinfunction "S_3") (pintype "passive"))
      (node (ref "X4") (pin "3") (pinfunction "S_3") (pintype "passive"))
    )
    (net (code "35") (name "Net-(IC3A-C)") (class "Default")
      (node (ref "IC3") (pin "12") (pinfunction "C_12") (pintype "input"))
      (node (ref "R29") (pin "1") (pinfunction "1_1") (pintype "passive"))
      (node (ref "X1") (pin "2") (pinfunction "2_2") (pintype "passive"))
      (node (ref "X3") (pin "4") (pinfunction "S_4") (pintype "passive"))
      (node (ref "X4") (pin "4") (pinfunction "S_4") (pintype "passive"))
    )
    (net (code "36") (name "Net-(IC3A-Q0)") (class "Default")
      (node (ref "IC3") (pin "3") (pinfunction "Q0_3") (pintype "output"))
      (node (ref "R25") (pin "2") (pinfunction "2_2") (pintype "passive"))
      (node (ref "R26") (pin "2") (pinfunction "2_2") (pintype "passive"))
    )
    (net (code "37") (name "Net-(IC3A-Q1)") (class "Default")
      (node (ref "IC3") (pin "14") (pinfunction "Q1_14") (pintype "output"))
      (node (ref "R36") (pin "2") (pinfunction "2_2") (pintype "passive"))
    )
    (net (code "38") (name "Net-(IC3A-Q2)") (class "Default")
      (node (ref "IC3") (pin "2") (pinfunction "Q2_2") (pintype "output"))
      (node (ref "R35") (pin "2") (pinfunction "2_2") (pintype "passive"))
    )
    (net (code "39") (name "Net-(IC3A-Q3)") (class "Default")
      (node (ref "IC3") (pin "15") (pinfunction "Q3_15") (pintype "output"))
      (node (ref "R34") (pin "2") (pinfunction "2_2") (pintype "passive"))
    )
    (net (code "40") (name "Net-(IC3A-Q4)") (class "Default")
      (node (ref "IC3") (pin "1") (pinfunction "Q4_1") (pintype "output"))
      (node (ref "R33") (pin "2") (pinfunction "2_2") (pintype "passive"))
    )
    (net (code "41") (name "Net-(IC3A-Q5)") (class "Default")
      (node (ref "IC3") (pin "6") (pinfunction "Q5_6") (pintype "output"))
      (node (ref "R32") (pin "2") (pinfunction "2_2") (pintype "passive"))
    )
    (net (code "42") (name "Net-(IC4-ADJ)") (class "Default")
      (node (ref "IC4") (pin "1") (pinfunction "ADJ_1") (pintype "input"))
      (node (ref "R18") (pin "1") (pinfunction "1_1") (pintype "passive"))
      (node (ref "R5") (pin "2") (pinfunction "2_2") (pintype "passive"))
      (node (ref "X1") (pin "7") (pinfunction "7_7") (pintype "passive"))
    )
    (net (code "43") (name "Net-(IC4-VI)") (class "Default")
      (node (ref "IC4") (pin "3") (pinfunction "VI_3") (pintype "input"))
      (node (ref "R37") (pin "1") (pinfunction "1_1") (pintype "passive"))
      (node (ref "T3") (pin "2") (pinfunction "C_2") (pintype "passive"))
    )
    (net (code "44") (name "Net-(IC4-VO)") (class "Default")
      (node (ref "IC4") (pin "2") (pinfunction "VO_2") (pintype "passive"))
      (node (ref "R18") (pin "2") (pinfunction "2_2") (pintype "passive"))
    )
    (net (code "45") (name "Net-(IC5A-+IN)") (class "Default")
      (node (ref "C3") (pin "1") (pinfunction "1_1") (pintype "passive"))
      (node (ref "IC5") (pin "3") (pinfunction "+IN_3") (pintype "input"))
      (node (ref "R12") (pin "1") (pinfunction "1_1") (pintype "passive"))
    )
    (net (code "46") (name "Net-(IC5A--IN)") (class "Default")
      (node (ref "IC5") (pin "2") (pinfunction "-IN_2") (pintype "input"))
      (node (ref "R15") (pin "1") (pinfunction "1_1") (pintype "passive"))
      (node (ref "R16") (pin "2") (pinfunction "2_2") (pintype "passive"))
      (node (ref "R17") (pin "2") (pinfunction "2_2") (pintype "passive"))
    )
    (net (code "47") (name "Net-(IC5A-OUT)") (class "Default")
      (node (ref "IC5") (pin "1") (pinfunction "OUT_1") (pintype "output"))
      (node (ref "R19") (pin "2") (pinfunction "2_2") (pintype "passive"))
      (node (ref "R21") (pin "2") (pinfunction "2_2") (pintype "passive"))
    )
    (net (code "48") (name "Net-(IC5B--IN)") (class "Default")
      (node (ref "IC5") (pin "6") (pinfunction "-IN_6") (pintype "input"))
      (node (ref "R7") (pin "1") (pinfunction "1_1") (pintype "passive"))
      (node (ref "R8") (pin "2") (pinfunction "2_2") (pintype "passive"))
    )
    (net (code "49") (name "Net-(IC5B-OUT)") (class "Default")
      (node (ref "IC5") (pin "7") (pinfunction "OUT_7") (pintype "output"))
      (node (ref "R9") (pin "2") (pinfunction "2_2") (pintype "passive"))
    )
    (net (code "50") (name "Net-(R1-Pad2)") (class "Default")
      (node (ref "R1") (pin "2") (pinfunction "2_2") (pintype "passive"))
      (node (ref "X1") (pin "22") (pinfunction "22_22") (pintype "passive"))
    )
    (net (code "51") (name "Net-(R3-Pad1)") (class "Default")
      (node (ref "R3") (pin "1") (pinfunction "1_1") (pintype "passive"))
      (node (ref "R4") (pin "1") (pinfunction "1_1") (pintype "passive"))
      (node (ref "T1") (pin "B") (pinfunction "B_B") (pintype "passive"))
    )
    (net (code "52") (name "Net-(R11-Pad1)") (class "Default")
      (node (ref "R11") (pin "1") (pinfunction "1_1") (pintype "passive"))
      (node (ref "R9") (pin "1") (pinfunction "1_1") (pintype "passive"))
      (node (ref "T2") (pin "B") (pinfunction "B_B") (pintype "passive"))
    )
    (net (code "53") (name "Net-(R13-Pad2)") (class "Default")
      (node (ref "R13") (pin "2") (pinfunction "2_2") (pintype "passive"))
      (node (ref "T2") (pin "C") (pinfunction "C_C") (pintype "passive"))
    )
    (net (code "54") (name "Net-(R17-Pad1)") (class "Default")
      (node (ref "R17") (pin "1") (pinfunction "1_1") (pintype "passive"))
      (node (ref "T4") (pin "C") (pinfunction "C_C") (pintype "passive"))
    )
    (net (code "55") (name "Net-(R19-Pad1)") (class "Default")
      (node (ref "R19") (pin "1") (pinfunction "1_1") (pintype "passive"))
      (node (ref "R20") (pin "1") (pinfunction "1_1") (pintype "passive"))
      (node (ref "T4") (pin "B") (pinfunction "B_B") (pintype "passive"))
    )
    (net (code "56") (name "Net-(R21-Pad1)") (class "Default")
      (node (ref "R21") (pin "1") (pinfunction "1_1") (pintype "passive"))
      (node (ref "R22") (pin "1") (pinfunction "1_1") (pintype "passive"))
      (node (ref "T5") (pin "B") (pinfunction "B_B") (pintype "passive"))
    )
    (net (code "57") (name "Net-(R24-Pad1)") (class "Default")
      (node (ref "R24") (pin "1") (pinfunction "1_1") (pintype "passive"))
      (node (ref "T6") (pin "C") (pinfunction "C_C") (pintype "passive"))
    )
    (net (code "58") (name "Net-(R25-Pad1)") (class "Default")
      (node (ref "R25") (pin "1") (pinfunction "1_1") (pintype "passive"))
      (node (ref "T6") (pin "B") (pinfunction "B_B") (pintype "passive"))
    )
    (net (code "59") (name "Net-(R26-Pad1)") (class "Default")
      (node (ref "R26") (pin "1") (pinfunction "1_1") (pintype "passive"))
      (node (ref "T7") (pin "B") (pinfunction "B_B") (pintype "passive"))
    )
    (net (code "60") (name "Net-(R27-Pad2)") (class "Default")
      (node (ref "R27") (pin "2") (pinfunction "2_2") (pintype "passive"))
      (node (ref "R28") (pin "1") (pinfunction "1_1") (pintype "passive"))
    )
    (net (code "61") (name "Net-(R32-Pad1)") (class "Default")
      (node (ref "R32") (pin "1") (pinfunction "1_1") (pintype "passive"))
      (node (ref "T8") (pin "B") (pinfunction "B_B") (pintype "passive"))
    )
    (net (code "62") (name "Net-(R33-Pad1)") (class "Default")
      (node (ref "R33") (pin "1") (pinfunction "1_1") (pintype "passive"))
      (node (ref "T9") (pin "B") (pinfunction "B_B") (pintype "passive"))
    )
    (net (code "63") (name "Net-(R34-Pad1)") (class "Default")
      (node (ref "R34") (pin "1") (pinfunction "1_1") (pintype "passive"))
      (node (ref "T10") (pin "B") (pinfunction "B_B") (pintype "passive"))
    )
    (net (code "64") (name "Net-(R35-Pad1)") (class "Default")
      (node (ref "R35") (pin "1") (pinfunction "1_1") (pintype "passive"))
      (node (ref "T11") (pin "B") (pinfunction "B_B") (pintype "passive"))
    )
    (net (code "65") (name "Net-(R36-Pad1)") (class "Default")
      (node (ref "R36") (pin "1") (pinfunction "1_1") (pintype "passive"))
      (node (ref "T12") (pin "B") (pinfunction "B_B") (pintype "passive"))
    )
    (net (code "66") (name "Net-(T-B)") (class "Default")
      (node (ref "R23") (pin "1") (pinfunction "1_1") (pintype "passive"))
      (node (ref "R24") (pin "2") (pinfunction "2_2") (pintype "passive"))
      (node (ref "T") (pin "1") (pinfunction "B_1") (pintype "passive"))
    )
    (net (code "67") (name "Net-(T3-B)") (class "Default")
      (node (ref "R13") (pin "1") (pinfunction "1_1") (pintype "passive"))
      (node (ref "R14") (pin "1") (pinfunction "1_1") (pintype "passive"))
      (node (ref "T3") (pin "1") (pinfunction "B_1") (pintype "passive"))
    )
    (net (code "68") (name "Net-(T13-B)") (class "Default")
      (node (ref "R38") (pin "2") (pinfunction "2_2") (pintype "passive"))
      (node (ref "R39") (pin "2") (pinfunction "2_2") (pintype "passive"))
      (node (ref "T13") (pin "1") (pinfunction "B_1") (pintype "passive"))
      (node (ref "T13") (pin "2") (pinfunction "C_2") (pintype "passive"))
      (node (ref "T14") (pin "1") (pinfunction "B_1") (pintype "passive"))
      (node (ref "X2") (pin "1") (pinfunction "S_1") (pintype "passive"))
    )
    (net (code "69") (name "Net-(T13-E)") (class "Default")
      (node (ref "R40") (pin "1") (pinfunction "1_1") (pintype "passive"))
      (node (ref "T13") (pin "3") (pinfunction "E_3") (pintype "passive"))
    )
    (net (code "70") (name "Net-(T14-E)") (class "Default")
      (node (ref "R41") (pin "1") (pinfunction "1_1") (pintype "passive"))
      (node (ref "T14") (pin "3") (pinfunction "E_3") (pintype "passive"))
    )
    (net (code "71") (name "Net-(TACHO_BELEUCHTUNG-PP)") (class "Default")
      (node (ref "TACHO_BELEUCHTUNG") (pin "TP") (pinfunction "PP_TP") (pintype "input"))
      (node (ref "X1") (pin "24") (pinfunction "24_24") (pintype "passive"))
    )
    (net (code "72") (name "Net-(ZüNDSPULE-PP)") (class "Default")
      (node (ref "X1") (pin "16") (pinfunction "16_16") (pintype "passive"))
      (node (ref "ZüNDSPULE") (pin "TP") (pinfunction "PP_TP") (pintype "input"))
    )
    (net (code "73") (name "VCC") (class "Default")
      (node (ref "C4") (pin "1") (pinfunction "1_1") (pintype "passive"))
      (node (ref "IC1") (pin "OUT") (pinfunction "OUT_OUT") (pintype "passive"))
      (node (ref "IC2") (pin "8") (pinfunction "V+_8") (pintype "power_in"))
      (node (ref "IC5") (pin "8") (pinfunction "V+_8") (pintype "power_in"))
      (node (ref "R15") (pin "2") (pinfunction "2_2") (pintype "passive"))
      (node (ref "R6") (pin "2") (pinfunction "2_2") (pintype "passive"))
    )
    (net (code "74") (name "unconnected-(IC3A-Q6-Pad7)") (class "Default")
      (node (ref "IC3") (pin "7") (pinfunction "Q6_7") (pintype "output"))
    )
    (net (code "75") (name "unconnected-(IC3A-Q7-Pad4)") (class "Default")
      (node (ref "IC3") (pin "4") (pinfunction "Q7_4") (pintype "output"))
    )
    (net (code "76") (name "unconnected-(IC3A-Q8-Pad9)") (class "Default")
      (node (ref "IC3") (pin "9") (pinfunction "Q8_9") (pintype "output"))
    )
    (net (code "77") (name "unconnected-(IC3A-Q9-Pad5)") (class "Default")
      (node (ref "IC3") (pin "5") (pinfunction "Q9_5") (pintype "output"))
    )
    (net (code "78") (name "unconnected-(T-C{slash}-Pad4)") (class "Default")
      (node (ref "T") (pin "4") (pinfunction "C/_4") (pintype "passive"))
    )
    (net (code "79") (name "unconnected-(T3-C{slash}-Pad4)") (class "Default")
      (node (ref "T3") (pin "4") (pinfunction "C/_4") (pintype "passive"))
    )
    (net (code "80") (name "unconnected-(T13-C{slash}-Pad4)") (class "Default")
      (node (ref "T13") (pin "4") (pinfunction "C/_4") (pintype "passive"))
    )
    (net (code "81") (name "unconnected-(T14-C{slash}-Pad4)") (class "Default")
      (node (ref "T14") (pin "4") (pinfunction "C/_4") (pintype "passive"))
    )
    (net (code "82") (name "unconnected-(X1-Pad20)") (class "Default")
      (node (ref "X1") (pin "20") (pinfunction "20_20") (pintype "passive"))
    )
  )
)
